# Noc_Informatyka_v1_1.net
KiCad netlist of a schematic drawn in EAGLE
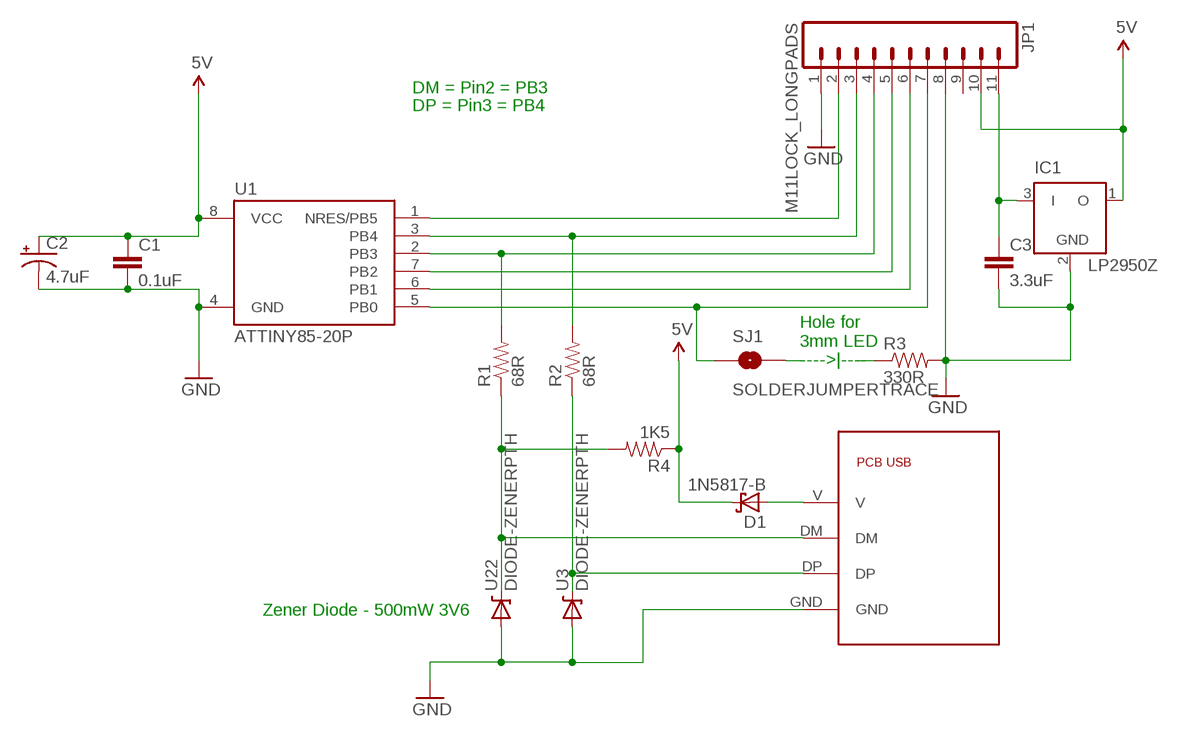
[diagram p0: schematic, sheet 1]

(export (version "E")
  (design (tool "Eeschema 10.0.6"))
  (components
    (comp (ref "C1")
      (value "0.1uF")
      (footprint "eagle-import:CAP-PTH-SMALLEZ")
      (libsource (lib "eagle-import") (part "CAPEZ"))
    )
    (comp (ref "C2")
      (value "4.7uF")
      (footprint "eagle-import:CPOL-RADIAL-10UF-25V")
      (libsource (lib "eagle-import") (part "CAP_POLPTH2"))
    )
    (comp (ref "C3")
      (value "3.3uF")
      (footprint "eagle-import:CAP-PTH-5MM")
      (libsource (lib "eagle-import") (part "CAPPTH1"))
    )
    (comp (ref "D1")
      (value "1N5817-B")
      (footprint "eagle-import:DO41-7.6")
      (libsource (lib "eagle-import") (part "1N5817-B"))
    )
    (comp (ref "IC1")
      (value "LP2950Z")
      (footprint "eagle-import:TO92")
      (libsource (lib "eagle-import") (part "LP2950Z"))
    )
    (comp (ref "JP1")
      (value "M11LOCK_LONGPADS")
      (footprint "eagle-import:1X11_LOCK_LONGPADS")
      (libsource (lib "eagle-import") (part "M11LOCK_LONGPADS"))
    )
    (comp (ref "R1")
      (value "68R")
      (footprint "eagle-import:AXIAL-0.3EZ")
      (libsource (lib "eagle-import") (part "SparkFun-Resistors_RESISTOREZ"))
    )
    (comp (ref "R2")
      (value "68R")
      (footprint "eagle-import:AXIAL-0.3EZ")
      (libsource (lib "eagle-import") (part "SparkFun-Resistors_RESISTOREZ"))
    )
    (comp (ref "R3")
      (value "330R")
      (footprint "eagle-import:AXIAL-0.3EZ")
      (libsource (lib "eagle-import") (part "RESISTOREZ"))
    )
    (comp (ref "R4")
      (value "1K5")
      (footprint "eagle-import:AXIAL-0.3EZ")
      (libsource (lib "eagle-import") (part "SparkFun-Resistors_RESISTOREZ"))
    )
    (comp (ref "SJ1")
      (value "SOLDERJUMPERTRACE")
      (footprint "eagle-import:SJ_2S-TRACE")
      (libsource (lib "eagle-import") (part "SOLDERJUMPERTRACE"))
    )
    (comp (ref "U$1")
      (value "PCB_USBNOBACK")
      (footprint "eagle-import:PCB_USB")
      (libsource (lib "eagle-import") (part "PCB_USBNOBACK"))
    )
    (comp (ref "U1")
      (value "ATTINY85-20P")
      (footprint "eagle-import:PDIP08_300MIL")
      (libsource (lib "eagle-import") (part "ATTINY85P-20"))
    )
    (comp (ref "U3")
      (value "DIODE-ZENERPTH")
      (footprint "eagle-import:DIODE-ZENER")
      (libsource (lib "eagle-import") (part "DIODE-ZENERPTH"))
    )
    (comp (ref "U22")
      (value "DIODE-ZENERPTH")
      (footprint "eagle-import:DIODE-ZENER")
      (libsource (lib "eagle-import") (part "DIODE-ZENERPTH"))
    )
  )
  (nets
    (net (code "1") (name "5V") (class "Default")
      (node (ref "C1") (pin "1") (pinfunction "1_1") (pintype "passive"))
      (node (ref "C2") (pin "1") (pinfunction "+_1") (pintype "passive"))
      (node (ref "D1") (pin "C") (pinfunction "C_C") (pintype "passive"))
      (node (ref "IC1") (pin "1") (pinfunction "O_1") (pintype "input"))
      (node (ref "JP1") (pin "10") (pinfunction "10_10") (pintype "passive"))
      (node (ref "R4") (pin "P$1") (pinfunction "1_P$1") (pintype "passive"))
      (node (ref "U1") (pin "8") (pinfunction "VCC_8") (pintype "power_in"))
    )
    (net (code "2") (name "GND") (class "Default")
      (node (ref "C1") (pin "2") (pinfunction "2_2") (pintype "passive"))
      (node (ref "C2") (pin "2") (pinfunction "-_2") (pintype "passive"))
      (node (ref "C3") (pin "2") (pinfunction "2_2") (pintype "passive"))
      (node (ref "IC1") (pin "2") (pinfunction "GND_2") (pintype "power_in"))
      (node (ref "JP1") (pin "1") (pinfunction "1_1") (pintype "passive"))
      (node (ref "JP1") (pin "8") (pinfunction "8_8") (pintype "passive"))
      (node (ref "R3") (pin "P$2") (pinfunction "2_P$2") (pintype "passive"))
      (node (ref "U$1") (pin "GND") (pinfunction "GND_GND") (pintype "bidirectional"))
      (node (ref "U1") (pin "4") (pinfunction "GND_4") (pintype "power_in"))
      (node (ref "U22") (pin "P$2") (pinfunction "A_P$2") (pintype "passive"))
      (node (ref "U3") (pin "P$2") (pinfunction "A_P$2") (pintype "passive"))
    )
    (net (code "3") (name "Net-(D1-PadA)") (class "Default")
      (node (ref "D1") (pin "A") (pinfunction "A_A") (pintype "passive"))
      (node (ref "U$1") (pin "V") (pinfunction "V_V") (pintype "bidirectional"))
    )
    (net (code "4") (name "Net-(IC1-I)") (class "Default")
      (node (ref "C3") (pin "1") (pinfunction "1_1") (pintype "passive"))
      (node (ref "IC1") (pin "3") (pinfunction "I_3") (pintype "input"))
      (node (ref "JP1") (pin "11") (pinfunction "11_11") (pintype "passive"))
    )
    (net (code "5") (name "Net-(R1-1)") (class "Default")
      (node (ref "R1") (pin "P$1") (pinfunction "1_P$1") (pintype "passive"))
      (node (ref "R4") (pin "P$2") (pinfunction "2_P$2") (pintype "passive"))
      (node (ref "U$1") (pin "DM") (pinfunction "DM_DM") (pintype "bidirectional"))
      (node (ref "U22") (pin "P$1") (pinfunction "C_P$1") (pintype "passive"))
    )
    (net (code "6") (name "Net-(R1-2)") (class "Default")
      (node (ref "JP1") (pin "4") (pinfunction "4_4") (pintype "passive"))
      (node (ref "R1") (pin "P$2") (pinfunction "2_P$2") (pintype "passive"))
      (node (ref "U1") (pin "2") (pinfunction "PB3_2") (pintype "bidirectional"))
    )
    (net (code "7") (name "Net-(R2-1)") (class "Default")
      (node (ref "R2") (pin "P$1") (pinfunction "1_P$1") (pintype "passive"))
      (node (ref "U$1") (pin "DP") (pinfunction "DP_DP") (pintype "bidirectional"))
      (node (ref "U3") (pin "P$1") (pinfunction "C_P$1") (pintype "passive"))
    )
    (net (code "8") (name "Net-(R2-2)") (class "Default")
      (node (ref "JP1") (pin "3") (pinfunction "3_3") (pintype "passive"))
      (node (ref "R2") (pin "P$2") (pinfunction "2_P$2") (pintype "passive"))
      (node (ref "U1") (pin "3") (pinfunction "PB4_3") (pintype "bidirectional"))
    )
    (net (code "9") (name "Net-(U1-NRES{slash}PB5)") (class "Default")
      (node (ref "JP1") (pin "2") (pinfunction "2_2") (pintype "passive"))
      (node (ref "U1") (pin "1") (pinfunction "NRES/PB5_1") (pintype "bidirectional"))
    )
    (net (code "10") (name "Net-(U1-PB0)") (class "Default")
      (node (ref "JP1") (pin "7") (pinfunction "7_7") (pintype "passive"))
      (node (ref "SJ1") (pin "1") (pinfunction "1_1") (pintype "passive"))
      (node (ref "U1") (pin "5") (pinfunction "PB0_5") (pintype "bidirectional"))
    )
    (net (code "11") (name "Net-(U1-PB1)") (class "Default")
      (node (ref "JP1") (pin "6") (pinfunction "6_6") (pintype "passive"))
      (node (ref "U1") (pin "6") (pinfunction "PB1_6") (pintype "bidirectional"))
    )
    (net (code "12") (name "Net-(U1-PB2)") (class "Default")
      (node (ref "JP1") (pin "5") (pinfunction "5_5") (pintype "passive"))
      (node (ref "U1") (pin "7") (pinfunction "PB2_7") (pintype "bidirectional"))
    )
    (net (code "13") (name "unconnected-(JP1-Pad9)") (class "Default")
      (node (ref "JP1") (pin "9") (pinfunction "9_9") (pintype "passive"))
    )
    (net (code "14") (name "unconnected-(R3-1-PadP$1)") (class "Default")
      (node (ref "R3") (pin "P$1") (pinfunction "1_P$1") (pintype "passive"))
    )
    (net (code "15") (name "unconnected-(SJ1-Pad2)") (class "Default")
      (node (ref "SJ1") (pin "2") (pinfunction "2_2") (pintype "passive"))
    )
  )
)
